# LinearOptoMixer.net
KiCad netlist of a schematic drawn in EAGLE
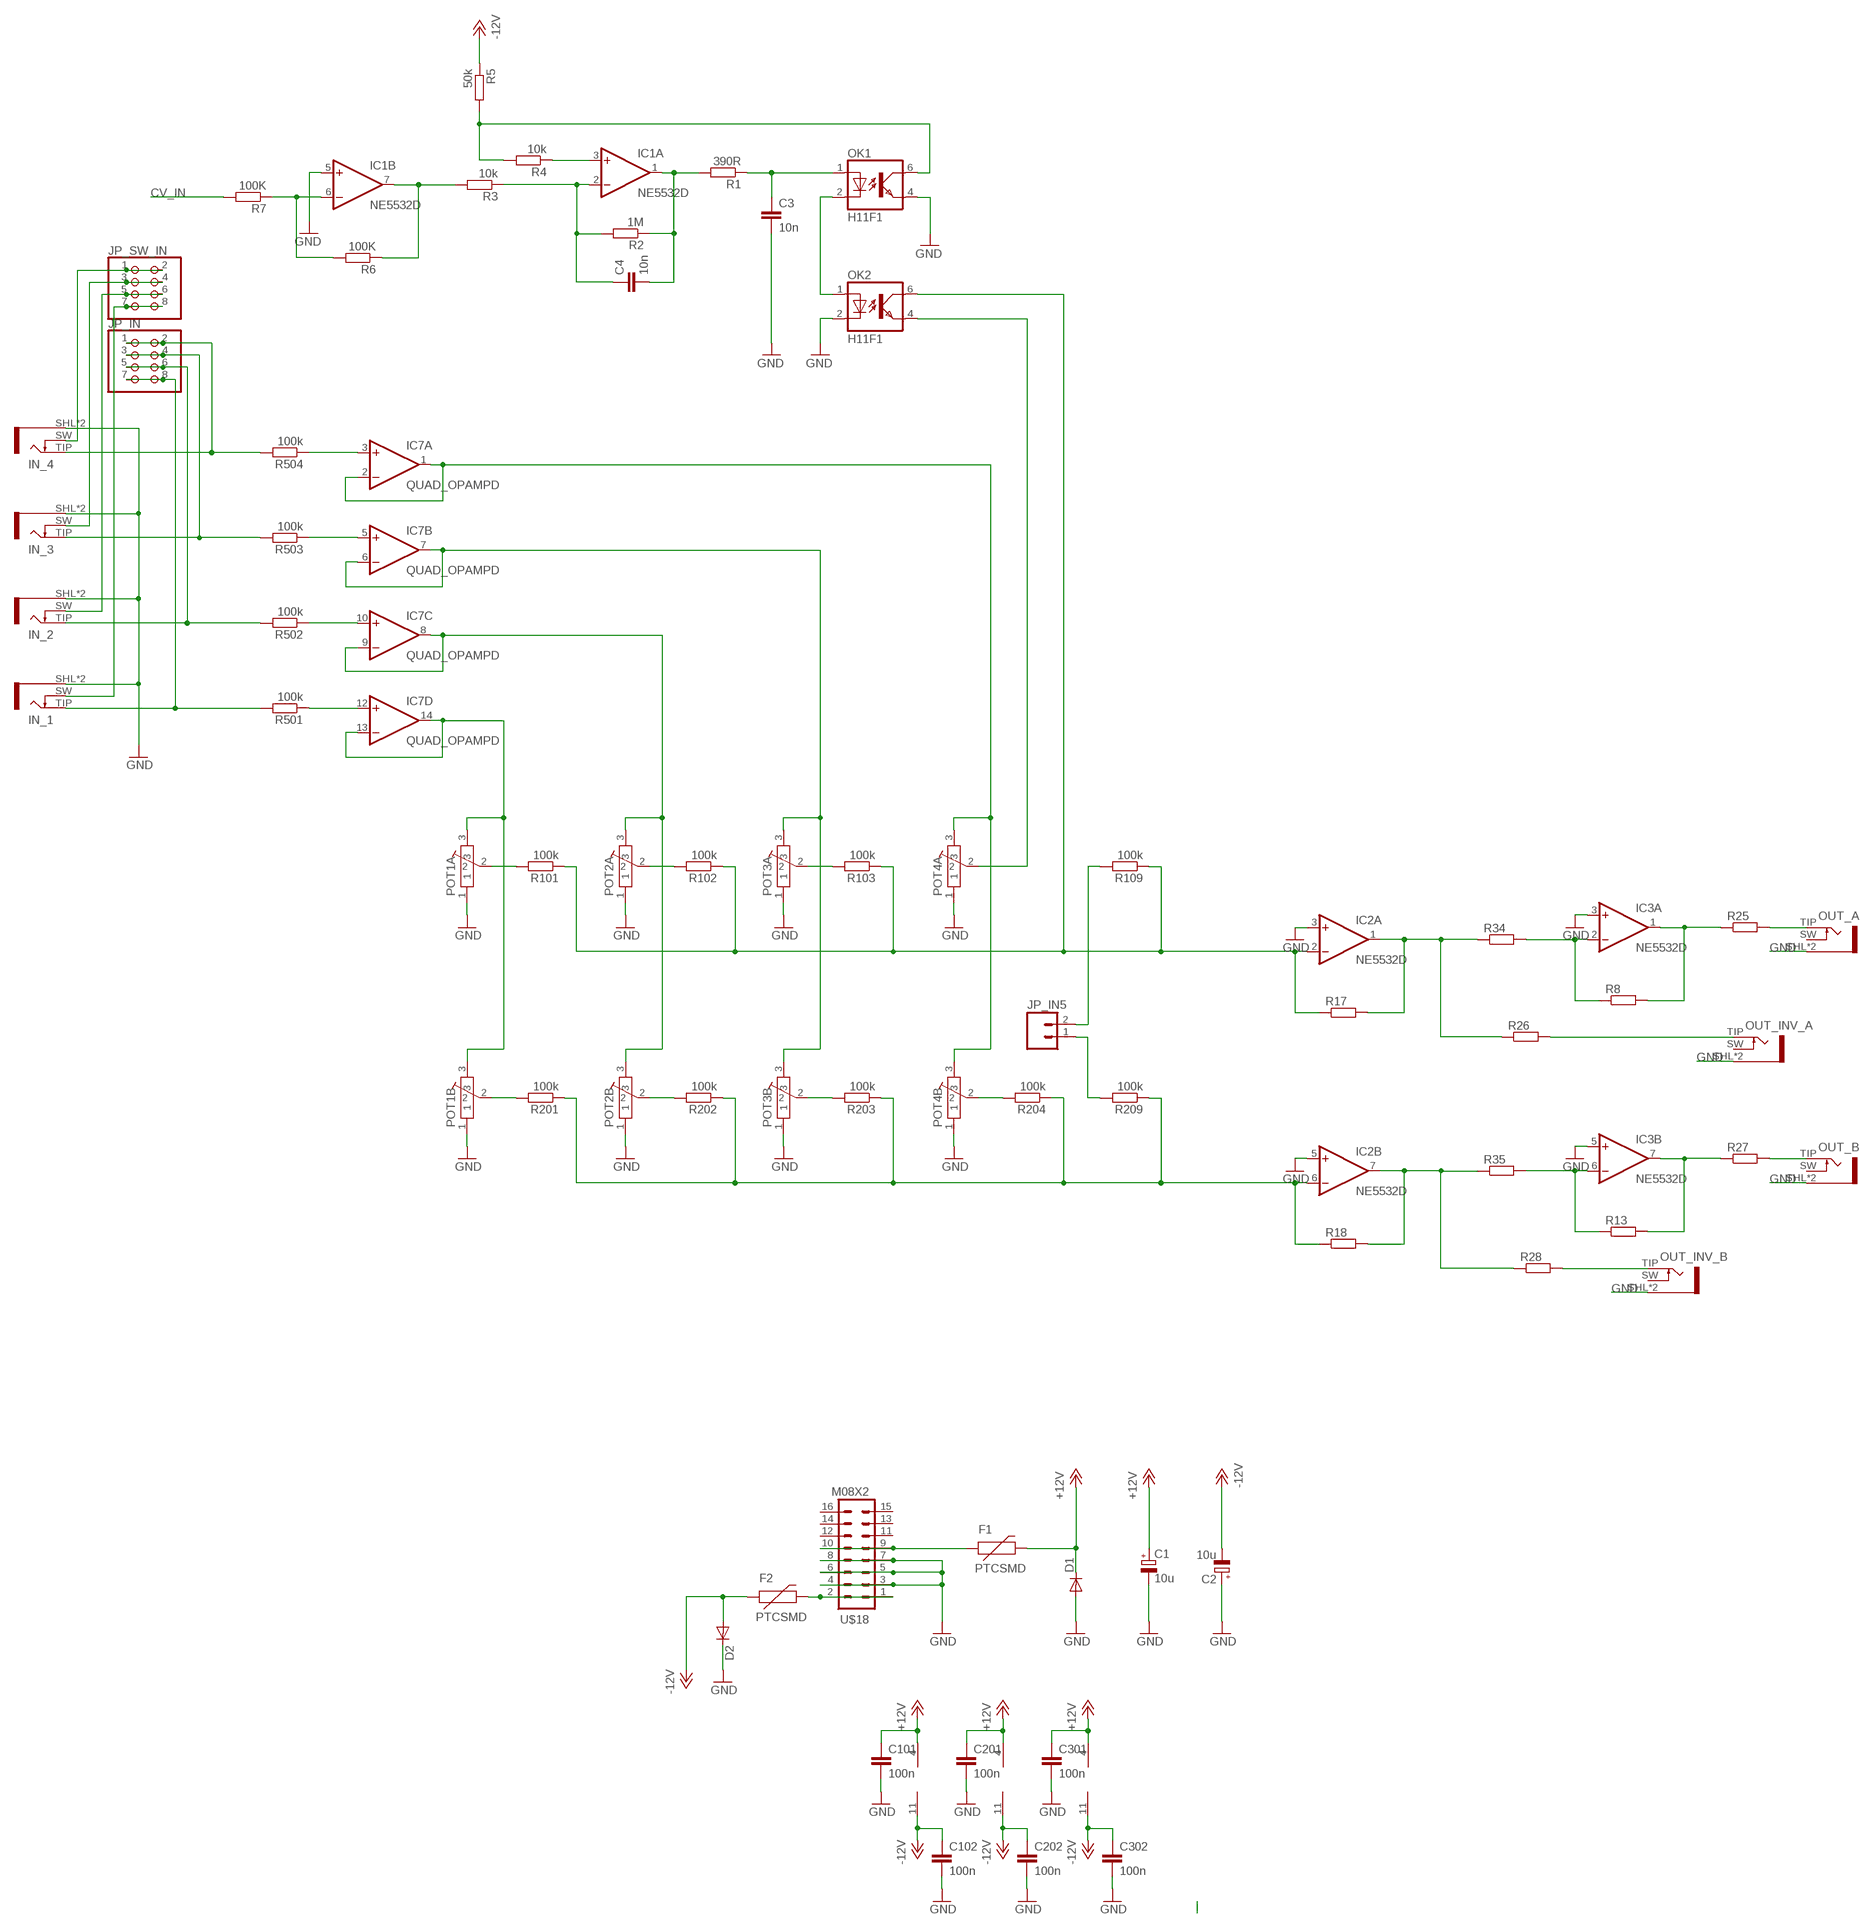
[diagram p0: schematic, sheet 1]

(export (version "E")
  (design (tool "Eeschema 10.0.6"))
  (components
    (comp (ref "C1")
      (value "10u")
      (footprint "eagle-import:PANASONIC_A")
      (libsource (lib "eagle-import") (part "CPOL-EUA"))
    )
    (comp (ref "C2")
      (value "10u")
      (footprint "eagle-import:PANASONIC_A")
      (libsource (lib "eagle-import") (part "CPOL-EUA"))
    )
    (comp (ref "C3")
      (value "10n")
      (footprint "eagle-import:C0603")
      (libsource (lib "eagle-import") (part "C-EUC0603"))
    )
    (comp (ref "C4")
      (value "10n")
      (footprint "eagle-import:C0603")
      (libsource (lib "eagle-import") (part "C-EUC0603"))
    )
    (comp (ref "C101")
      (value "100n")
      (footprint "eagle-import:C0603")
      (libsource (lib "eagle-import") (part "C-EUC0603"))
    )
    (comp (ref "C102")
      (value "100n")
      (footprint "eagle-import:C0603")
      (libsource (lib "eagle-import") (part "C-EUC0603"))
    )
    (comp (ref "C201")
      (value "100n")
      (footprint "eagle-import:C0603")
      (libsource (lib "eagle-import") (part "C-EUC0603"))
    )
    (comp (ref "C202")
      (value "100n")
      (footprint "eagle-import:C0603")
      (libsource (lib "eagle-import") (part "C-EUC0603"))
    )
    (comp (ref "C301")
      (value "100n")
      (footprint "eagle-import:C0603")
      (libsource (lib "eagle-import") (part "C-EUC0603"))
    )
    (comp (ref "C302")
      (value "100n")
      (footprint "eagle-import:C0603")
      (libsource (lib "eagle-import") (part "C-EUC0603"))
    )
    (comp (ref "D1")
      (value "DIODESMA")
      (footprint "eagle-import:SMA-DIODE")
      (libsource (lib "eagle-import") (part "DIODESMA"))
    )
    (comp (ref "D2")
      (value "DIODESMA")
      (footprint "eagle-import:SMA-DIODE")
      (libsource (lib "eagle-import") (part "DIODESMA"))
    )
    (comp (ref "F1")
      (value "PTCSMD")
      (footprint "eagle-import:PTC-1206")
      (libsource (lib "eagle-import") (part "PTCSMD"))
    )
    (comp (ref "F2")
      (value "PTCSMD")
      (footprint "eagle-import:PTC-1206")
      (libsource (lib "eagle-import") (part "PTCSMD"))
    )
    (comp (ref "IC1")
      (value "NE5532D")
      (footprint "eagle-import:SO08")
      (libsource (lib "eagle-import") (part "NE5532D"))
    )
    (comp (ref "IC2")
      (value "NE5532D")
      (footprint "eagle-import:SO08")
      (libsource (lib "eagle-import") (part "NE5532D"))
    )
    (comp (ref "IC3")
      (value "NE5532D")
      (footprint "eagle-import:SO08")
      (libsource (lib "eagle-import") (part "NE5532D"))
    )
    (comp (ref "IC4")
      (value "QUAD_OPAMPD")
      (footprint "eagle-import:SO14")
      (libsource (lib "eagle-import") (part "QUAD_OPAMPD"))
    )
    (comp (ref "IC5")
      (value "QUAD_OPAMPD")
      (footprint "eagle-import:SO14")
      (libsource (lib "eagle-import") (part "QUAD_OPAMPD"))
    )
    (comp (ref "IC6")
      (value "QUAD_OPAMPD")
      (footprint "eagle-import:SO14")
      (libsource (lib "eagle-import") (part "QUAD_OPAMPD"))
    )
    (comp (ref "IC7")
      (value "QUAD_OPAMPD")
      (footprint "eagle-import:SO14")
      (libsource (lib "eagle-import") (part "QUAD_OPAMPD"))
    )
    (comp (ref "IN_1")
      (value "JACK-PJ-301B")
      (footprint "eagle-import:PJ-301B")
      (libsource (lib "eagle-import") (part "JACK-PJ-301B"))
    )
    (comp (ref "IN_2")
      (value "JACK-PJ-301B")
      (footprint "eagle-import:PJ-301B")
      (libsource (lib "eagle-import") (part "JACK-PJ-301B"))
    )
    (comp (ref "IN_3")
      (value "JACK-PJ-301B")
      (footprint "eagle-import:PJ-301B")
      (libsource (lib "eagle-import") (part "JACK-PJ-301B"))
    )
    (comp (ref "IN_4")
      (value "JACK-PJ-301B")
      (footprint "eagle-import:PJ-301B")
      (libsource (lib "eagle-import") (part "JACK-PJ-301B"))
    )
    (comp (ref "JP_IN")
      (value "PINHD-2X4")
      (footprint "eagle-import:2X04")
      (libsource (lib "eagle-import") (part "PINHD-2X4"))
    )
    (comp (ref "JP_IN5")
      (value "M02PTH")
      (footprint "eagle-import:1X02")
      (libsource (lib "eagle-import") (part "M02PTH"))
    )
    (comp (ref "JP_SW_IN")
      (value "PINHD-2X4")
      (footprint "eagle-import:2X04")
      (libsource (lib "eagle-import") (part "PINHD-2X4"))
    )
    (comp (ref "OK1")
      (value "H11F1")
      (footprint "eagle-import:DIL05")
      (fields (field (name "OC_FARNELL") "unknown") (field (name "OC_NEWARK") "unknown"))
      (libsource (lib "eagle-import") (part "H11F1"))
    )
    (comp (ref "OK2")
      (value "H11F1")
      (footprint "eagle-import:DIL05")
      (fields (field (name "OC_FARNELL") "unknown") (field (name "OC_NEWARK") "unknown"))
      (libsource (lib "eagle-import") (part "H11F1"))
    )
    (comp (ref "OUT_A")
      (value "JACK-PJ-301B")
      (footprint "eagle-import:PJ-301B")
      (libsource (lib "eagle-import") (part "JACK-PJ-301B"))
    )
    (comp (ref "OUT_B")
      (value "JACK-PJ-301B")
      (footprint "eagle-import:PJ-301B")
      (libsource (lib "eagle-import") (part "JACK-PJ-301B"))
    )
    (comp (ref "OUT_INV_A")
      (value "JACK-PJ-301B")
      (footprint "eagle-import:PJ-301B")
      (libsource (lib "eagle-import") (part "JACK-PJ-301B"))
    )
    (comp (ref "OUT_INV_B")
      (value "JACK-PJ-301B")
      (footprint "eagle-import:PJ-301B")
      (libsource (lib "eagle-import") (part "JACK-PJ-301B"))
    )
    (comp (ref "POT1A")
      (value "POT-ALPS-RK09L1140")
      (footprint "eagle-import:POT-ALPS-RK09L1140")
      (libsource (lib "eagle-import") (part "POT-ALPS-RK09L1140"))
    )
    (comp (ref "POT1B")
      (value "POT-ALPS-RK09L1140")
      (footprint "eagle-import:POT-ALPS-RK09L1140")
      (libsource (lib "eagle-import") (part "POT-ALPS-RK09L1140"))
    )
    (comp (ref "POT2A")
      (value "POT-ALPS-RK09L1140")
      (footprint "eagle-import:POT-ALPS-RK09L1140")
      (libsource (lib "eagle-import") (part "POT-ALPS-RK09L1140"))
    )
    (comp (ref "POT2B")
      (value "POT-ALPS-RK09L1140")
      (footprint "eagle-import:POT-ALPS-RK09L1140")
      (libsource (lib "eagle-import") (part "POT-ALPS-RK09L1140"))
    )
    (comp (ref "POT3A")
      (value "POT-ALPS-RK09L1140")
      (footprint "eagle-import:POT-ALPS-RK09L1140")
      (libsource (lib "eagle-import") (part "POT-ALPS-RK09L1140"))
    )
    (comp (ref "POT3B")
      (value "POT-ALPS-RK09L1140")
      (footprint "eagle-import:POT-ALPS-RK09L1140")
      (libsource (lib "eagle-import") (part "POT-ALPS-RK09L1140"))
    )
    (comp (ref "POT4A")
      (value "POT-ALPS-RK09L1140")
      (footprint "eagle-import:POT-ALPS-RK09L1140")
      (libsource (lib "eagle-import") (part "POT-ALPS-RK09L1140"))
    )
    (comp (ref "POT4B")
      (value "POT-ALPS-RK09L1140")
      (footprint "eagle-import:POT-ALPS-RK09L1140")
      (libsource (lib "eagle-import") (part "POT-ALPS-RK09L1140"))
    )
    (comp (ref "R1")
      (value "390R")
      (footprint "eagle-import:R0603")
      (libsource (lib "eagle-import") (part "R-EU_R0603"))
    )
    (comp (ref "R2")
      (value "1M")
      (footprint "eagle-import:R0603")
      (libsource (lib "eagle-import") (part "R-EU_R0603"))
    )
    (comp (ref "R3")
      (value "10k")
      (footprint "eagle-import:R0603")
      (libsource (lib "eagle-import") (part "R-EU_R0603"))
    )
    (comp (ref "R4")
      (value "10k")
      (footprint "eagle-import:R0603")
      (libsource (lib "eagle-import") (part "R-EU_R0603"))
    )
    (comp (ref "R5")
      (value "50k")
      (footprint "eagle-import:R0603")
      (libsource (lib "eagle-import") (part "R-EU_R0603"))
    )
    (comp (ref "R6")
      (value "100K")
      (footprint "eagle-import:R0603")
      (libsource (lib "eagle-import") (part "R-EU_R0603"))
    )
    (comp (ref "R7")
      (value "100K")
      (footprint "eagle-import:R0603")
      (libsource (lib "eagle-import") (part "R-EU_R0603"))
    )
    (comp (ref "R8")
      (value "R-EU_R0603")
      (footprint "eagle-import:R0603")
      (libsource (lib "eagle-import") (part "R-EU_R0603"))
    )
    (comp (ref "R13")
      (value "R-EU_R0603")
      (footprint "eagle-import:R0603")
      (libsource (lib "eagle-import") (part "R-EU_R0603"))
    )
    (comp (ref "R17")
      (value "R-EU_R0603")
      (footprint "eagle-import:R0603")
      (libsource (lib "eagle-import") (part "R-EU_R0603"))
    )
    (comp (ref "R18")
      (value "R-EU_R0603")
      (footprint "eagle-import:R0603")
      (libsource (lib "eagle-import") (part "R-EU_R0603"))
    )
    (comp (ref "R25")
      (value "R-EU_R0603")
      (footprint "eagle-import:R0603")
      (libsource (lib "eagle-import") (part "R-EU_R0603"))
    )
    (comp (ref "R26")
      (value "R-EU_R0603")
      (footprint "eagle-import:R0603")
      (libsource (lib "eagle-import") (part "R-EU_R0603"))
    )
    (comp (ref "R27")
      (value "R-EU_R0603")
      (footprint "eagle-import:R0603")
      (libsource (lib "eagle-import") (part "R-EU_R0603"))
    )
    (comp (ref "R28")
      (value "R-EU_R0603")
      (footprint "eagle-import:R0603")
      (libsource (lib "eagle-import") (part "R-EU_R0603"))
    )
    (comp (ref "R34")
      (value "R-EU_R0603")
      (footprint "eagle-import:R0603")
      (libsource (lib "eagle-import") (part "R-EU_R0603"))
    )
    (comp (ref "R35")
      (value "R-EU_R0603")
      (footprint "eagle-import:R0603")
      (libsource (lib "eagle-import") (part "R-EU_R0603"))
    )
    (comp (ref "R101")
      (value "100k")
      (footprint "eagle-import:R0603")
      (libsource (lib "eagle-import") (part "R-EU_R0603"))
    )
    (comp (ref "R102")
      (value "100k")
      (footprint "eagle-import:R0603")
      (libsource (lib "eagle-import") (part "R-EU_R0603"))
    )
    (comp (ref "R103")
      (value "100k")
      (footprint "eagle-import:R0603")
      (libsource (lib "eagle-import") (part "R-EU_R0603"))
    )
    (comp (ref "R109")
      (value "100k")
      (footprint "eagle-import:R0603")
      (libsource (lib "eagle-import") (part "R-EU_R0603"))
    )
    (comp (ref "R201")
      (value "100k")
      (footprint "eagle-import:R0603")
      (libsource (lib "eagle-import") (part "R-EU_R0603"))
    )
    (comp (ref "R202")
      (value "100k")
      (footprint "eagle-import:R0603")
      (libsource (lib "eagle-import") (part "R-EU_R0603"))
    )
    (comp (ref "R203")
      (value "100k")
      (footprint "eagle-import:R0603")
      (libsource (lib "eagle-import") (part "R-EU_R0603"))
    )
    (comp (ref "R204")
      (value "100k")
      (footprint "eagle-import:R0603")
      (libsource (lib "eagle-import") (part "R-EU_R0603"))
    )
    (comp (ref "R209")
      (value "100k")
      (footprint "eagle-import:R0603")
      (libsource (lib "eagle-import") (part "R-EU_R0603"))
    )
    (comp (ref "R501")
      (value "100k")
      (footprint "eagle-import:R0603")
      (libsource (lib "eagle-import") (part "R-EU_R0603"))
    )
    (comp (ref "R502")
      (value "100k")
      (footprint "eagle-import:R0603")
      (libsource (lib "eagle-import") (part "R-EU_R0603"))
    )
    (comp (ref "R503")
      (value "100k")
      (footprint "eagle-import:R0603")
      (libsource (lib "eagle-import") (part "R-EU_R0603"))
    )
    (comp (ref "R504")
      (value "100k")
      (footprint "eagle-import:R0603")
      (libsource (lib "eagle-import") (part "R-EU_R0603"))
    )
    (comp (ref "U$18")
      (value "M08X2")
      (footprint "eagle-import:2X8")
      (libsource (lib "eagle-import") (part "M08X2"))
    )
  )
  (nets
    (net (code "1") (name "+12V") (class "Default")
      (node (ref "C1") (pin "+") (pinfunction "+_+") (pintype "passive"))
      (node (ref "C101") (pin "1") (pinfunction "1_1") (pintype "passive"))
      (node (ref "C201") (pin "1") (pinfunction "1_1") (pintype "passive"))
      (node (ref "C301") (pin "1") (pinfunction "1_1") (pintype "passive"))
      (node (ref "D1") (pin "C") (pinfunction "C_C") (pintype "passive"))
      (node (ref "F1") (pin "2") (pinfunction "2_2") (pintype "bidirectional"))
      (node (ref "IC4") (pin "4") (pinfunction "V+_4") (pintype "power_in"))
      (node (ref "IC5") (pin "4") (pinfunction "V+_4") (pintype "power_in"))
      (node (ref "IC6") (pin "4") (pinfunction "V+_4") (pintype "power_in"))
    )
    (net (code "2") (name "-12V") (class "Default")
      (node (ref "C102") (pin "1") (pinfunction "1_1") (pintype "passive"))
      (node (ref "C2") (pin "-") (pinfunction "-_-") (pintype "passive"))
      (node (ref "C202") (pin "1") (pinfunction "1_1") (pintype "passive"))
      (node (ref "C302") (pin "1") (pinfunction "1_1") (pintype "passive"))
      (node (ref "D2") (pin "A") (pinfunction "A_A") (pintype "passive"))
      (node (ref "F2") (pin "1") (pinfunction "1_1") (pintype "bidirectional"))
      (node (ref "IC4") (pin "11") (pinfunction "V-_11") (pintype "power_in"))
      (node (ref "IC5") (pin "11") (pinfunction "V-_11") (pintype "power_in"))
      (node (ref "IC6") (pin "11") (pinfunction "V-_11") (pintype "power_in"))
      (node (ref "R5") (pin "1") (pinfunction "1_1") (pintype "passive"))
    )
    (net (code "3") (name "/CV_IN") (class "Default")
      (node (ref "R7") (pin "2") (pinfunction "2_2") (pintype "passive"))
    )
    (net (code "4") (name "GND") (class "Default")
      (node (ref "C1") (pin "-") (pinfunction "-_-") (pintype "passive"))
      (node (ref "C101") (pin "2") (pinfunction "2_2") (pintype "passive"))
      (node (ref "C102") (pin "2") (pinfunction "2_2") (pintype "passive"))
      (node (ref "C2") (pin "+") (pinfunction "+_+") (pintype "passive"))
      (node (ref "C201") (pin "2") (pinfunction "2_2") (pintype "passive"))
      (node (ref "C202") (pin "2") (pinfunction "2_2") (pintype "passive"))
      (node (ref "C3") (pin "2") (pinfunction "2_2") (pintype "passive"))
      (node (ref "C301") (pin "2") (pinfunction "2_2") (pintype "passive"))
      (node (ref "C302") (pin "2") (pinfunction "2_2") (pintype "passive"))
      (node (ref "D1") (pin "A") (pinfunction "A_A") (pintype "passive"))
      (node (ref "D2") (pin "C") (pinfunction "C_C") (pintype "passive"))
      (node (ref "IC1") (pin "5") (pinfunction "+IN_5") (pintype "input"))
      (node (ref "IC2") (pin "3") (pinfunction "+IN_3") (pintype "input"))
      (node (ref "IC2") (pin "5") (pinfunction "+IN_5") (pintype "input"))
      (node (ref "IC3") (pin "3") (pinfunction "+IN_3") (pintype "input"))
      (node (ref "IC3") (pin "5") (pinfunction "+IN_5") (pintype "input"))
      (node (ref "IN_1") (pin "SHL") (pinfunction "SLEEVE_SHL") (pintype "passive"))
      (node (ref "IN_1") (pin "SLV") (pinfunction "SLEEVE_SLV") (pintype "passive"))
      (node (ref "IN_2") (pin "SHL") (pinfunction "SLEEVE_SHL") (pintype "passive"))
      (node (ref "IN_2") (pin "SLV") (pinfunction "SLEEVE_SLV") (pintype "passive"))
      (node (ref "IN_3") (pin "SHL") (pinfunction "SLEEVE_SHL") (pintype "passive"))
      (node (ref "IN_3") (pin "SLV") (pinfunction "SLEEVE_SLV") (pintype "passive"))
      (node (ref "IN_4") (pin "SHL") (pinfunction "SLEEVE_SHL") (pintype "passive"))
      (node (ref "IN_4") (pin "SLV") (pinfunction "SLEEVE_SLV") (pintype "passive"))
      (node (ref "OK1") (pin "4") (pinfunction "EMIT_4") (pintype "passive"))
      (node (ref "OK2") (pin "2") (pinfunction "C_2") (pintype "passive"))
      (node (ref "OUT_A") (pin "SHL") (pinfunction "SLEEVE_SHL") (pintype "passive"))
      (node (ref "OUT_A") (pin "SLV") (pinfunction "SLEEVE_SLV") (pintype "passive"))
      (node (ref "OUT_B") (pin "SHL") (pinfunction "SLEEVE_SHL") (pintype "passive"))
      (node (ref "OUT_B") (pin "SLV") (pinfunction "SLEEVE_SLV") (pintype "passive"))
      (node (ref "OUT_INV_A") (pin "SHL") (pinfunction "SLEEVE_SHL") (pintype "passive"))
      (node (ref "OUT_INV_A") (pin "SLV") (pinfunction "SLEEVE_SLV") (pintype "passive"))
      (node (ref "OUT_INV_B") (pin "SHL") (pinfunction "SLEEVE_SHL") (pintype "passive"))
      (node (ref "OUT_INV_B") (pin "SLV") (pinfunction "SLEEVE_SLV") (pintype "passive"))
      (node (ref "POT1A") (pin "1") (pinfunction "1_1") (pintype "bidirectional"))
      (node (ref "POT1B") (pin "1") (pinfunction "1_1") (pintype "bidirectional"))
      (node (ref "POT2A") (pin "1") (pinfunction "1_1") (pintype "bidirectional"))
      (node (ref "POT2B") (pin "1") (pinfunction "1_1") (pintype "bidirectional"))
      (node (ref "POT3A") (pin "1") (pinfunction "1_1") (pintype "bidirectional"))
      (node (ref "POT3B") (pin "1") (pinfunction "1_1") (pintype "bidirectional"))
      (node (ref "POT4A") (pin "1") (pinfunction "1_1") (pintype "bidirectional"))
      (node (ref "POT4B") (pin "1") (pinfunction "1_1") (pintype "bidirectional"))
      (node (ref "U$18") (pin "3") (pinfunction "3_3") (pintype "passive"))
      (node (ref "U$18") (pin "4") (pinfunction "4_4") (pintype "passive"))
      (node (ref "U$18") (pin "5") (pinfunction "5_5") (pintype "passive"))
      (node (ref "U$18") (pin "6") (pinfunction "6_6") (pintype "passive"))
      (node (ref "U$18") (pin "7") (pinfunction "7_7") (pintype "passive"))
      (node (ref "U$18") (pin "8") (pinfunction "8_8") (pintype "passive"))
    )
    (net (code "5") (name "Net-(F1-Pad1)") (class "Default")
      (node (ref "F1") (pin "1") (pinfunction "1_1") (pintype "bidirectional"))
      (node (ref "U$18") (pin "10") (pinfunction "10_10") (pintype "passive"))
      (node (ref "U$18") (pin "9") (pinfunction "9_9") (pintype "passive"))
    )
    (net (code "6") (name "Net-(F2-Pad2)") (class "Default")
      (node (ref "F2") (pin "2") (pinfunction "2_2") (pintype "bidirectional"))
      (node (ref "U$18") (pin "1") (pinfunction "1_1") (pintype "passive"))
      (node (ref "U$18") (pin "2") (pinfunction "2_2") (pintype "passive"))
    )
    (net (code "7") (name "Net-(IC1A-+IN)") (class "Default")
      (node (ref "IC1") (pin "3") (pinfunction "+IN_3") (pintype "input"))
      (node (ref "R4") (pin "1") (pinfunction "1_1") (pintype "passive"))
    )
    (net (code "8") (name "Net-(IC1A--IN)") (class "Default")
      (node (ref "C4") (pin "1") (pinfunction "1_1") (pintype "passive"))
      (node (ref "IC1") (pin "2") (pinfunction "-IN_2") (pintype "input"))
      (node (ref "R2") (pin "2") (pinfunction "2_2") (pintype "passive"))
      (node (ref "R3") (pin "1") (pinfunction "1_1") (pintype "passive"))
    )
    (net (code "9") (name "Net-(IC1A-OUT)") (class "Default")
      (node (ref "C4") (pin "2") (pinfunction "2_2") (pintype "passive"))
      (node (ref "IC1") (pin "1") (pinfunction "OUT_1") (pintype "output"))
      (node (ref "R1") (pin "2") (pinfunction "2_2") (pintype "passive"))
      (node (ref "R2") (pin "1") (pinfunction "1_1") (pintype "passive"))
    )
    (net (code "10") (name "Net-(IC1B--IN)") (class "Default")
      (node (ref "IC1") (pin "6") (pinfunction "-IN_6") (pintype "input"))
      (node (ref "R6") (pin "2") (pinfunction "2_2") (pintype "passive"))
      (node (ref "R7") (pin "1") (pinfunction "1_1") (pintype "passive"))
    )
    (net (code "11") (name "Net-(IC1B-OUT)") (class "Default")
      (node (ref "IC1") (pin "7") (pinfunction "OUT_7") (pintype "output"))
      (node (ref "R3") (pin "2") (pinfunction "2_2") (pintype "passive"))
      (node (ref "R6") (pin "1") (pinfunction "1_1") (pintype "passive"))
    )
    (net (code "12") (name "Net-(IC2A--IN)") (class "Default")
      (node (ref "IC2") (pin "2") (pinfunction "-IN_2") (pintype "input"))
      (node (ref "OK2") (pin "6") (pinfunction "COL_6") (pintype "passive"))
      (node (ref "R101") (pin "1") (pinfunction "1_1") (pintype "passive"))
      (node (ref "R102") (pin "1") (pinfunction "1_1") (pintype "passive"))
      (node (ref "R103") (pin "1") (pinfunction "1_1") (pintype "passive"))
      (node (ref "R109") (pin "1") (pinfunction "1_1") (pintype "passive"))
      (node (ref "R17") (pin "1") (pinfunction "1_1") (pintype "passive"))
    )
    (net (code "13") (name "Net-(IC2A-OUT)") (class "Default")
      (node (ref "IC2") (pin "1") (pinfunction "OUT_1") (pintype "output"))
      (node (ref "R17") (pin "2") (pinfunction "2_2") (pintype "passive"))
      (node (ref "R26") (pin "1") (pinfunction "1_1") (pintype "passive"))
      (node (ref "R34") (pin "1") (pinfunction "1_1") (pintype "passive"))
    )
    (net (code "14") (name "Net-(IC2B--IN)") (class "Default")
      (node (ref "IC2") (pin "6") (pinfunction "-IN_6") (pintype "input"))
      (node (ref "R18") (pin "1") (pinfunction "1_1") (pintype "passive"))
      (node (ref "R201") (pin "1") (pinfunction "1_1") (pintype "passive"))
      (node (ref "R202") (pin "1") (pinfunction "1_1") (pintype "passive"))
      (node (ref "R203") (pin "1") (pinfunction "1_1") (pintype "passive"))
      (node (ref "R204") (pin "1") (pinfunction "1_1") (pintype "passive"))
      (node (ref "R209") (pin "1") (pinfunction "1_1") (pintype "passive"))
    )
    (net (code "15") (name "Net-(IC2B-OUT)") (class "Default")
      (node (ref "IC2") (pin "7") (pinfunction "OUT_7") (pintype "output"))
      (node (ref "R18") (pin "2") (pinfunction "2_2") (pintype "passive"))
      (node (ref "R28") (pin "1") (pinfunction "1_1") (pintype "passive"))
      (node (ref "R35") (pin "1") (pinfunction "1_1") (pintype "passive"))
    )
    (net (code "16") (name "Net-(IC3A--IN)") (class "Default")
      (node (ref "IC3") (pin "2") (pinfunction "-IN_2") (pintype "input"))
      (node (ref "R34") (pin "2") (pinfunction "2_2") (pintype "passive"))
      (node (ref "R8") (pin "1") (pinfunction "1_1") (pintype "passive"))
    )
    (net (code "17") (name "Net-(IC3A-OUT)") (class "Default")
      (node (ref "IC3") (pin "1") (pinfunction "OUT_1") (pintype "output"))
      (node (ref "R25") (pin "1") (pinfunction "1_1") (pintype "passive"))
      (node (ref "R8") (pin "2") (pinfunction "2_2") (pintype "passive"))
    )
    (net (code "18") (name "Net-(IC3B--IN)") (class "Default")
      (node (ref "IC3") (pin "6") (pinfunction "-IN_6") (pintype "input"))
      (node (ref "R13") (pin "1") (pinfunction "1_1") (pintype "passive"))
      (node (ref "R35") (pin "2") (pinfunction "2_2") (pintype "passive"))
    )
    (net (code "19") (name "Net-(IC3B-OUT)") (class "Default")
      (node (ref "IC3") (pin "7") (pinfunction "OUT_7") (pintype "output"))
      (node (ref "R13") (pin "2") (pinfunction "2_2") (pintype "passive"))
      (node (ref "R27") (pin "1") (pinfunction "1_1") (pintype "passive"))
    )
    (net (code "20") (name "Net-(IC7A-+IN)") (class "Default")
      (node (ref "IC7") (pin "3") (pinfunction "+IN_3") (pintype "input"))
      (node (ref "R504") (pin "1") (pinfunction "1_1") (pintype "passive"))
    )
    (net (code "21") (name "Net-(IC7A--IN)") (class "Default")
      (node (ref "IC7") (pin "1") (pinfunction "OUT_1") (pintype "output"))
      (node (ref "IC7") (pin "2") (pinfunction "-IN_2") (pintype "input"))
      (node (ref "POT4A") (pin "3") (pinfunction "3_3") (pintype "bidirectional"))
      (node (ref "POT4B") (pin "3") (pinfunction "3_3") (pintype "bidirectional"))
    )
    (net (code "22") (name "Net-(IC7B-+IN)") (class "Default")
      (node (ref "IC7") (pin "5") (pinfunction "+IN_5") (pintype "input"))
      (node (ref "R503") (pin "1") (pinfunction "1_1") (pintype "passive"))
    )
    (net (code "23") (name "Net-(IC7B--IN)") (class "Default")
      (node (ref "IC7") (pin "6") (pinfunction "-IN_6") (pintype "input"))
      (node (ref "IC7") (pin "7") (pinfunction "OUT_7") (pintype "output"))
      (node (ref "POT3A") (pin "3") (pinfunction "3_3") (pintype "bidirectional"))
      (node (ref "POT3B") (pin "3") (pinfunction "3_3") (pintype "bidirectional"))
    )
    (net (code "24") (name "Net-(IC7C-+IN)") (class "Default")
      (node (ref "IC7") (pin "10") (pinfunction "+IN_10") (pintype "input"))
      (node (ref "R502") (pin "1") (pinfunction "1_1") (pintype "passive"))
    )
    (net (code "25") (name "Net-(IC7C--IN)") (class "Default")
      (node (ref "IC7") (pin "8") (pinfunction "OUT_8") (pintype "output"))
      (node (ref "IC7") (pin "9") (pinfunction "-IN_9") (pintype "input"))
      (node (ref "POT2A") (pin "3") (pinfunction "3_3") (pintype "bidirectional"))
      (node (ref "POT2B") (pin "3") (pinfunction "3_3") (pintype "bidirectional"))
    )
    (net (code "26") (name "Net-(IC7D-+IN)") (class "Default")
      (node (ref "IC7") (pin "12") (pinfunction "+IN_12") (pintype "input"))
      (node (ref "R501") (pin "1") (pinfunction "1_1") (pintype "passive"))
    )
    (net (code "27") (name "Net-(IC7D--IN)") (class "Default")
      (node (ref "IC7") (pin "13") (pinfunction "-IN_13") (pintype "input"))
      (node (ref "IC7") (pin "14") (pinfunction "OUT_14") (pintype "output"))
      (node (ref "POT1A") (pin "3") (pinfunction "3_3") (pintype "bidirectional"))
      (node (ref "POT1B") (pin "3") (pinfunction "3_3") (pintype "bidirectional"))
    )
    (net (code "28") (name "Net-(IN_1-PadSW)") (class "Default")
      (node (ref "IN_1") (pin "SW") (pinfunction "SW_SW") (pintype "passive"))
      (node (ref "JP_SW_IN") (pin "7") (pinfunction "7_7") (pintype "passive"))
      (node (ref "JP_SW_IN") (pin "8") (pinfunction "8_8") (pintype "passive"))
    )
    (net (code "29") (name "Net-(IN_1-PadTIP)") (class "Default")
      (node (ref "IN_1") (pin "TIP") (pinfunction "TIP_TIP") (pintype "passive"))
      (node (ref "JP_IN") (pin "7") (pinfunction "7_7") (pintype "passive"))
      (node (ref "JP_IN") (pin "8") (pinfunction "8_8") (pintype "passive"))
      (node (ref "R501") (pin "2") (pinfunction "2_2") (pintype "passive"))
    )
    (net (code "30") (name "Net-(IN_2-PadSW)") (class "Default")
      (node (ref "IN_2") (pin "SW") (pinfunction "SW_SW") (pintype "passive"))
      (node (ref "JP_SW_IN") (pin "5") (pinfunction "5_5") (pintype "passive"))
      (node (ref "JP_SW_IN") (pin "6") (pinfunction "6_6") (pintype "passive"))
    )
    (net (code "31") (name "Net-(IN_2-PadTIP)") (class "Default")
      (node (ref "IN_2") (pin "TIP") (pinfunction "TIP_TIP") (pintype "passive"))
      (node (ref "JP_IN") (pin "5") (pinfunction "5_5") (pintype "passive"))
      (node (ref "JP_IN") (pin "6") (pinfunction "6_6") (pintype "passive"))
      (node (ref "R502") (pin "2") (pinfunction "2_2") (pintype "passive"))
    )
    (net (code "32") (name "Net-(IN_3-PadSW)") (class "Default")
      (node (ref "IN_3") (pin "SW") (pinfunction "SW_SW") (pintype "passive"))
      (node (ref "JP_SW_IN") (pin "3") (pinfunction "3_3") (pintype "passive"))
      (node (ref "JP_SW_IN") (pin "4") (pinfunction "4_4") (pintype "passive"))
    )
    (net (code "33") (name "Net-(IN_3-PadTIP)") (class "Default")
      (node (ref "IN_3") (pin "TIP") (pinfunction "TIP_TIP") (pintype "passive"))
      (node (ref "JP_IN") (pin "3") (pinfunction "3_3") (pintype "passive"))
      (node (ref "JP_IN") (pin "4") (pinfunction "4_4") (pintype "passive"))
      (node (ref "R503") (pin "2") (pinfunction "2_2") (pintype "passive"))
    )
    (net (code "34") (name "Net-(IN_4-PadSW)") (class "Default")
      (node (ref "IN_4") (pin "SW") (pinfunction "SW_SW") (pintype "passive"))
      (node (ref "JP_SW_IN") (pin "1") (pinfunction "1_1") (pintype "passive"))
      (node (ref "JP_SW_IN") (pin "2") (pinfunction "2_2") (pintype "passive"))
    )
    (net (code "35") (name "Net-(IN_4-PadTIP)") (class "Default")
      (node (ref "IN_4") (pin "TIP") (pinfunction "TIP_TIP") (pintype "passive"))
      (node (ref "JP_IN") (pin "1") (pinfunction "1_1") (pintype "passive"))
      (node (ref "JP_IN") (pin "2") (pinfunction "2_2") (pintype "passive"))
      (node (ref "R504") (pin "2") (pinfunction "2_2") (pintype "passive"))
    )
    (net (code "36") (name "Net-(JP_IN5-Pad1)") (class "Default")
      (node (ref "JP_IN5") (pin "1") (pinfunction "1_1") (pintype "passive"))
      (node (ref "R209") (pin "2") (pinfunction "2_2") (pintype "passive"))
    )
    (net (code "37") (name "Net-(JP_IN5-Pad2)") (class "Default")
      (node (ref "JP_IN5") (pin "2") (pinfunction "2_2") (pintype "passive"))
      (node (ref "R109") (pin "2") (pinfunction "2_2") (pintype "passive"))
    )
    (net (code "38") (name "Net-(OK1-A)") (class "Default")
      (node (ref "C3") (pin "1") (pinfunction "1_1") (pintype "passive"))
      (node (ref "OK1") (pin "1") (pinfunction "A_1") (pintype "passive"))
      (node (ref "R1") (pin "1") (pinfunction "1_1") (pintype "passive"))
    )
    (net (code "39") (name "Net-(OK1-C)") (class "Default")
      (node (ref "OK1") (pin "2") (pinfunction "C_2") (pintype "passive"))
      (node (ref "OK2") (pin "1") (pinfunction "A_1") (pintype "passive"))
    )
    (net (code "40") (name "Net-(OK1-COL)") (class "Default")
      (node (ref "OK1") (pin "6") (pinfunction "COL_6") (pintype "passive"))
      (node (ref "R4") (pin "2") (pinfunction "2_2") (pintype "passive"))
      (node (ref "R5") (pin "2") (pinfunction "2_2") (pintype "passive"))
    )
    (net (code "41") (name "Net-(OK2-EMIT)") (class "Default")
      (node (ref "OK2") (pin "4") (pinfunction "EMIT_4") (pintype "passive"))
      (node (ref "POT4A") (pin "2") (pinfunction "2_2") (pintype "bidirectional"))
    )
    (net (code "42") (name "Net-(OUT_A-PadTIP)") (class "Default")
      (node (ref "OUT_A") (pin "TIP") (pinfunction "TIP_TIP") (pintype "passive"))
      (node (ref "R25") (pin "2") (pinfunction "2_2") (pintype "passive"))
    )
    (net (code "43") (name "Net-(OUT_B-PadTIP)") (class "Default")
      (node (ref "OUT_B") (pin "TIP") (pinfunction "TIP_TIP") (pintype "passive"))
      (node (ref "R27") (pin "2") (pinfunction "2_2") (pintype "passive"))
    )
    (net (code "44") (name "Net-(OUT_INV_A-PadTIP)") (class "Default")
      (node (ref "OUT_INV_A") (pin "TIP") (pinfunction "TIP_TIP") (pintype "passive"))
      (node (ref "R26") (pin "2") (pinfunction "2_2") (pintype "passive"))
    )
    (net (code "45") (name "Net-(OUT_INV_B-PadTIP)") (class "Default")
      (node (ref "OUT_INV_B") (pin "TIP") (pinfunction "TIP_TIP") (pintype "passive"))
      (node (ref "R28") (pin "2") (pinfunction "2_2") (pintype "passive"))
    )
    (net (code "46") (name "Net-(POT1A-Pad2)") (class "Default")
      (node (ref "POT1A") (pin "2") (pinfunction "2_2") (pintype "bidirectional"))
      (node (ref "R101") (pin "2") (pinfunction "2_2") (pintype "passive"))
    )
    (net (code "47") (name "Net-(POT1B-Pad2)") (class "Default")
      (node (ref "POT1B") (pin "2") (pinfunction "2_2") (pintype "bidirectional"))
      (node (ref "R201") (pin "2") (pinfunction "2_2") (pintype "passive"))
    )
    (net (code "48") (name "Net-(POT2A-Pad2)") (class "Default")
      (node (ref "POT2A") (pin "2") (pinfunction "2_2") (pintype "bidirectional"))
      (node (ref "R102") (pin "2") (pinfunction "2_2") (pintype "passive"))
    )
    (net (code "49") (name "Net-(POT2B-Pad2)") (class "Default")
      (node (ref "POT2B") (pin "2") (pinfunction "2_2") (pintype "bidirectional"))
      (node (ref "R202") (pin "2") (pinfunction "2_2") (pintype "passive"))
    )
    (net (code "50") (name "Net-(POT3A-Pad2)") (class "Default")
      (node (ref "POT3A") (pin "2") (pinfunction "2_2") (pintype "bidirectional"))
      (node (ref "R103") (pin "2") (pinfunction "2_2") (pintype "passive"))
    )
    (net (code "51") (name "Net-(POT3B-Pad2)") (class "Default")
      (node (ref "POT3B") (pin "2") (pinfunction "2_2") (pintype "bidirectional"))
      (node (ref "R203") (pin "2") (pinfunction "2_2") (pintype "passive"))
    )
    (net (code "52") (name "Net-(POT4B-Pad2)") (class "Default")
      (node (ref "POT4B") (pin "2") (pinfunction "2_2") (pintype "bidirectional"))
      (node (ref "R204") (pin "2") (pinfunction "2_2") (pintype "passive"))
    )
    (net (code "53") (name "unconnected-(OUT_A-PadSW)") (class "Default")
      (node (ref "OUT_A") (pin "SW") (pinfunction "SW_SW") (pintype "passive"))
    )
    (net (code "54") (name "unconnected-(OUT_B-PadSW)") (class "Default")
      (node (ref "OUT_B") (pin "SW") (pinfunction "SW_SW") (pintype "passive"))
    )
    (net (code "55") (name "unconnected-(OUT_INV_A-PadSW)") (class "Default")
      (node (ref "OUT_INV_A") (pin "SW") (pinfunction "SW_SW") (pintype "passive"))
    )
    (net (code "56") (name "unconnected-(OUT_INV_B-PadSW)") (class "Default")
      (node (ref "OUT_INV_B") (pin "SW") (pinfunction "SW_SW") (pintype "passive"))
    )
    (net (code "57") (name "unconnected-(U$18-Pad11)") (class "Default")
      (node (ref "U$18") (pin "11") (pinfunction "11_11") (pintype "passive"))
    )
    (net (code "58") (name "unconnected-(U$18-Pad12)") (class "Default")
      (node (ref "U$18") (pin "12") (pinfunction "12_12") (pintype "passive"))
    )
    (net (code "59") (name "unconnected-(U$18-Pad13)") (class "Default")
      (node (ref "U$18") (pin "13") (pinfunction "13_13") (pintype "passive"))
    )
    (net (code "60") (name "unconnected-(U$18-Pad14)") (class "Default")
      (node (ref "U$18") (pin "14") (pinfunction "14_14") (pintype "passive"))
    )
    (net (code "61") (name "unconnected-(U$18-Pad15)") (class "Default")
      (node (ref "U$18") (pin "15") (pinfunction "15_15") (pintype "passive"))
    )
    (net (code "62") (name "unconnected-(U$18-Pad16)") (class "Default")
      (node (ref "U$18") (pin "16") (pinfunction "16_16") (pintype "passive"))
    )
  )
)
